# DS3_CONTROLLER_R.net
KiCad netlist of a schematic drawn in EasyEDA Pro
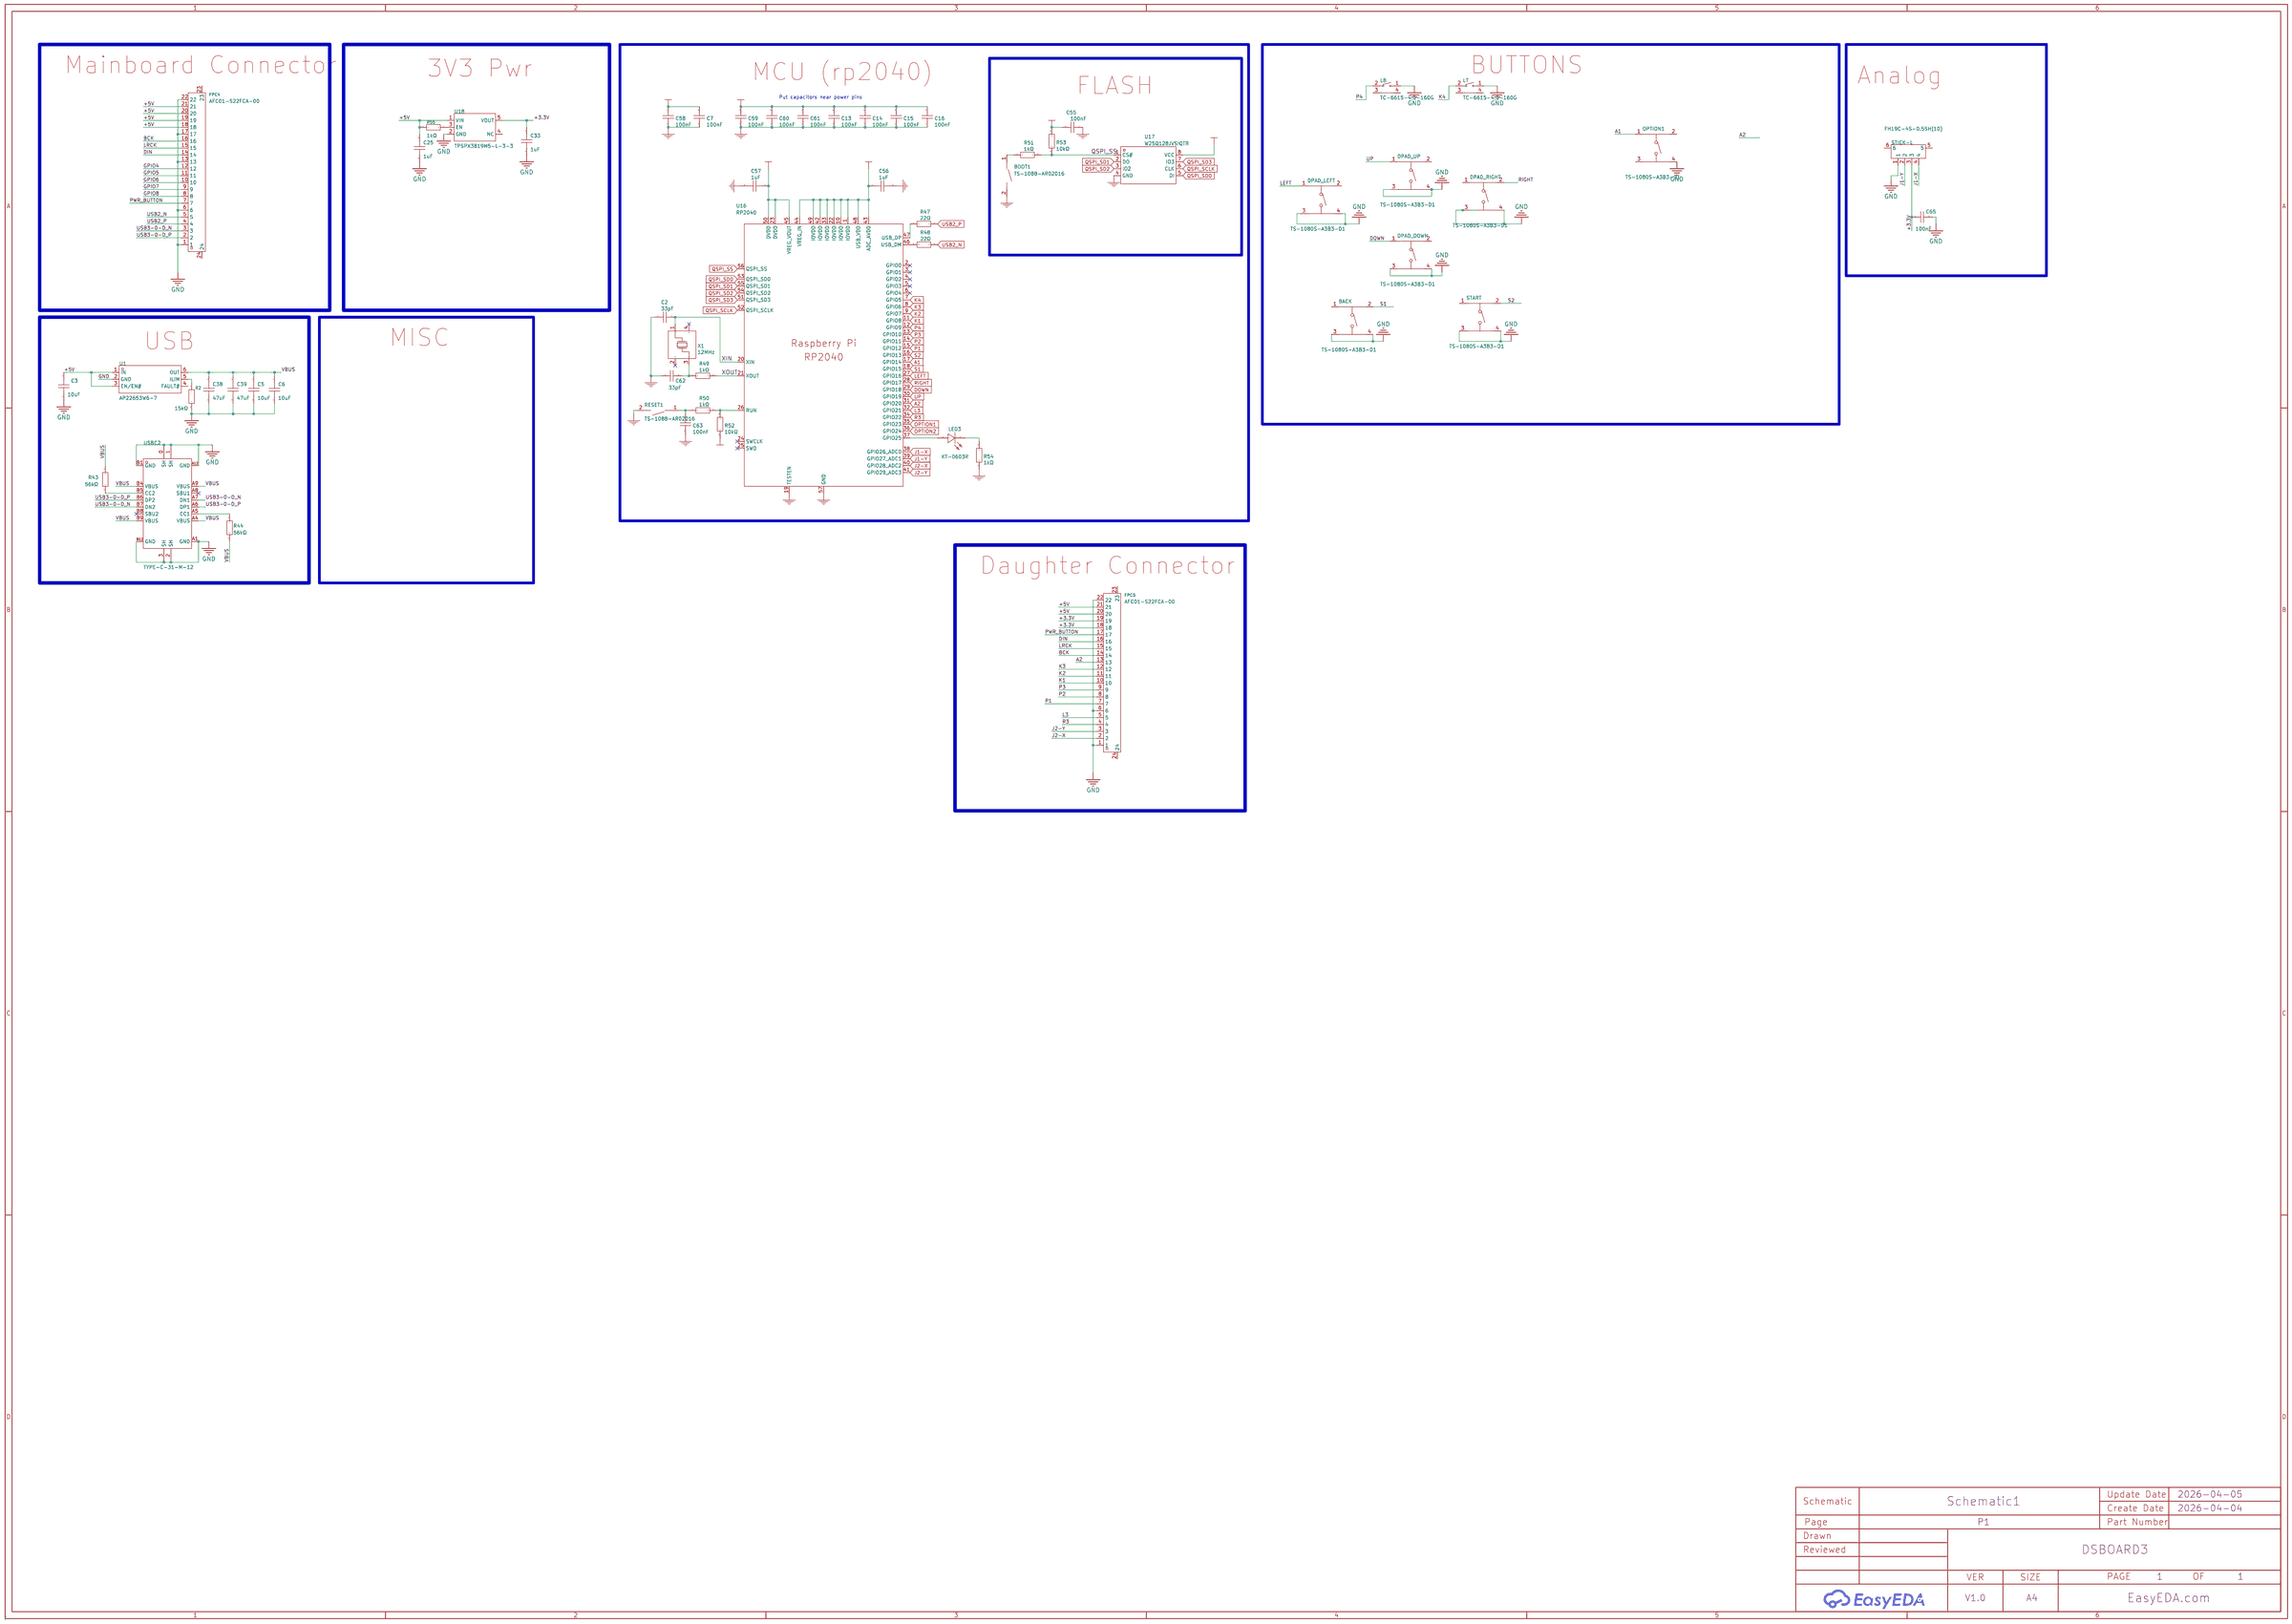
[diagram p0: schematic sheet]

(export (version "E")
  (design (tool "Eeschema 10.0.6"))
  (components
    (comp (ref "BACK")
      (value "TS-1080S-A3B3-D1")
      (footprint "easyedapro:KEY-SMD_4P-L6.0-W6.0-P4.50-LS9.5-BL")
      (fields (field (name "Manufacturer") "Yuandi(元迪)"))
      (libsource (lib "easyedapro") (part "K2-1102SP-C4SC-04"))
    )
    (comp (ref "BOOT1")
      (value "TS-1088-AR02016")
      (footprint "easyedapro:SW-SMD_L3.9-W3.0-P4.45")
      (fields (field (name "Manufacturer") "XUNPU(讯普)"))
      (libsource (lib "easyedapro") (part "TS-1088-AR02016"))
    )
    (comp (ref "C2")
      (value "33pF")
      (footprint "easyedapro:C0402")
      (fields (field (name "Manufacturer Part") "0402CG330J500NT") (field (name "Manufacturer") "FH(风华)"))
      (libsource (lib "easyedapro") (part "33pF"))
    )
    (comp (ref "C3")
      (value "10uF")
      (footprint "easyedapro:C0805")
      (fields
        (field (name "Manufacturer Part") "CL21A106KAYNNNE")
        (field (name "Manufacturer") "SAMSUNG(三星)")
      )
      (libsource (lib "easyedapro") (part "CL21A106KAYNNNE"))
    )
    (comp (ref "C5")
      (value "10uF")
      (footprint "easyedapro:C0805")
      (fields
        (field (name "Manufacturer Part") "CL21A106KAYNNNE")
        (field (name "Manufacturer") "SAMSUNG(三星)")
      )
      (libsource (lib "easyedapro") (part "CL21A106KAYNNNE"))
    )
    (comp (ref "C6")
      (value "10uF")
      (footprint "easyedapro:C0805")
      (fields
        (field (name "Manufacturer Part") "CL21A106KAYNNNE")
        (field (name "Manufacturer") "SAMSUNG(三星)")
      )
      (libsource (lib "easyedapro") (part "CL21A106KAYNNNE"))
    )
    (comp (ref "C7")
      (value "100nF")
      (footprint "easyedapro:C0402_NEW")
      (fields
        (field (name "Manufacturer Part") "CL05B104KO5NNNC")
        (field (name "Manufacturer") "SAMSUNG(三星)")
      )
      (libsource (lib "easyedapro") (part "100nF"))
    )
    (comp (ref "C13")
      (value "100nF")
      (footprint "easyedapro:C0402_NEW")
      (fields
        (field (name "Manufacturer Part") "CL05B104KO5NNNC")
        (field (name "Manufacturer") "SAMSUNG(三星)")
      )
      (libsource (lib "easyedapro") (part "100nF"))
    )
    (comp (ref "C14")
      (value "100nF")
      (footprint "easyedapro:C0402_NEW")
      (fields
        (field (name "Manufacturer Part") "CL05B104KO5NNNC")
        (field (name "Manufacturer") "SAMSUNG(三星)")
      )
      (libsource (lib "easyedapro") (part "100nF"))
    )
    (comp (ref "C15")
      (value "100nF")
      (footprint "easyedapro:C0402_NEW")
      (fields
        (field (name "Manufacturer Part") "CL05B104KO5NNNC")
        (field (name "Manufacturer") "SAMSUNG(三星)")
      )
      (libsource (lib "easyedapro") (part "100nF"))
    )
    (comp (ref "C16")
      (value "100nF")
      (footprint "easyedapro:C0402_NEW")
      (fields
        (field (name "Manufacturer Part") "CL05B104KO5NNNC")
        (field (name "Manufacturer") "SAMSUNG(三星)")
      )
      (libsource (lib "easyedapro") (part "100nF"))
    )
    (comp (ref "C25")
      (value "1uF")
      (footprint "easyedapro:C0603")
      (fields
        (field (name "Manufacturer Part") "CL10A105KB8NNNC")
        (field (name "Manufacturer") "SAMSUNG(三星)")
      )
      (libsource (lib "easyedapro") (part "CL10A105KB8NNNC"))
    )
    (comp (ref "C33")
      (value "1uF")
      (footprint "easyedapro:C0603")
      (fields
        (field (name "Manufacturer Part") "CL10A105KB8NNNC")
        (field (name "Manufacturer") "SAMSUNG(三星)")
      )
      (libsource (lib "easyedapro") (part "CL10A105KB8NNNC"))
    )
    (comp (ref "C38")
      (value "47uF")
      (footprint "easyedapro:C1206")
      (fields
        (field (name "Manufacturer Part") "CL31A476MPHNNNE")
        (field (name "Manufacturer") "SAMSUNG(三星)")
      )
      (libsource (lib "easyedapro") (part "CL31A476MPHNNNE"))
    )
    (comp (ref "C39")
      (value "47uF")
      (footprint "easyedapro:C1206")
      (fields
        (field (name "Manufacturer Part") "CL31A476MPHNNNE")
        (field (name "Manufacturer") "SAMSUNG(三星)")
      )
      (libsource (lib "easyedapro") (part "CL31A476MPHNNNE"))
    )
    (comp (ref "C55")
      (value "100nF")
      (footprint "easyedapro:C0402_NEW")
      (fields
        (field (name "Manufacturer Part") "CL05B104KO5NNNC")
        (field (name "Manufacturer") "SAMSUNG(三星)")
      )
      (libsource (lib "easyedapro") (part "100nF"))
    )
    (comp (ref "C56")
      (value "1uF")
      (footprint "easyedapro:C0402")
      (fields
        (field (name "Manufacturer Part") "CL05A105KA5NQNC")
        (field (name "Manufacturer") "SAMSUNG(三星)")
      )
      (libsource (lib "easyedapro") (part "1uF"))
    )
    (comp (ref "C57")
      (value "1uF")
      (footprint "easyedapro:C0402")
      (fields
        (field (name "Manufacturer Part") "CL05A105KA5NQNC")
        (field (name "Manufacturer") "SAMSUNG(三星)")
      )
      (libsource (lib "easyedapro") (part "1uF"))
    )
    (comp (ref "C58")
      (value "100nF")
      (footprint "easyedapro:C0402_NEW")
      (fields
        (field (name "Manufacturer Part") "CL05B104KO5NNNC")
        (field (name "Manufacturer") "SAMSUNG(三星)")
      )
      (libsource (lib "easyedapro") (part "100nF"))
    )
    (comp (ref "C59")
      (value "100nF")
      (footprint "easyedapro:C0402_NEW")
      (fields
        (field (name "Manufacturer Part") "CL05B104KO5NNNC")
        (field (name "Manufacturer") "SAMSUNG(三星)")
      )
      (libsource (lib "easyedapro") (part "100nF"))
    )
    (comp (ref "C60")
      (value "100nF")
      (footprint "easyedapro:C0402_NEW")
      (fields
        (field (name "Manufacturer Part") "CL05B104KO5NNNC")
        (field (name "Manufacturer") "SAMSUNG(三星)")
      )
      (libsource (lib "easyedapro") (part "100nF"))
    )
    (comp (ref "C61")
      (value "100nF")
      (footprint "easyedapro:C0402_NEW")
      (fields
        (field (name "Manufacturer Part") "CL05B104KO5NNNC")
        (field (name "Manufacturer") "SAMSUNG(三星)")
      )
      (libsource (lib "easyedapro") (part "100nF"))
    )
    (comp (ref "C62")
      (value "33pF")
      (footprint "easyedapro:C0402")
      (fields (field (name "Manufacturer Part") "0402CG330J500NT") (field (name "Manufacturer") "FH(风华)"))
      (libsource (lib "easyedapro") (part "33pF"))
    )
    (comp (ref "C63")
      (value "100nF")
      (footprint "easyedapro:C0402_NEW")
      (fields
        (field (name "Manufacturer Part") "CL05B104KO5NNNC")
        (field (name "Manufacturer") "SAMSUNG(三星)")
      )
      (libsource (lib "easyedapro") (part "100nF"))
    )
    (comp (ref "C65")
      (value "100nF")
      (footprint "easyedapro:C0402_NEW")
      (fields
        (field (name "Manufacturer Part") "CL05B104KO5NNNC")
        (field (name "Manufacturer") "SAMSUNG(三星)")
      )
      (libsource (lib "easyedapro") (part "100nF"))
    )
    (comp (ref "DPAD_DOWN")
      (value "TS-1080S-A3B3-D1")
      (footprint "easyedapro:KEY-SMD_4P-L6.0-W6.0-P4.50-LS9.5-BL")
      (fields (field (name "Manufacturer") "Yuandi(元迪)"))
      (libsource (lib "easyedapro") (part "K2-1102SP-C4SC-04"))
    )
    (comp (ref "DPAD_LEFT")
      (value "TS-1080S-A3B3-D1")
      (footprint "easyedapro:KEY-SMD_4P-L6.0-W6.0-P4.50-LS9.5-BL")
      (fields (field (name "Manufacturer") "Yuandi(元迪)"))
      (libsource (lib "easyedapro") (part "K2-1102SP-C4SC-04"))
    )
    (comp (ref "DPAD_RIGHT")
      (value "TS-1080S-A3B3-D1")
      (footprint "easyedapro:KEY-SMD_4P-L6.0-W6.0-P4.50-LS9.5-BL")
      (fields (field (name "Manufacturer") "Yuandi(元迪)"))
      (libsource (lib "easyedapro") (part "K2-1102SP-C4SC-04"))
    )
    (comp (ref "DPAD_UP")
      (value "TS-1080S-A3B3-D1")
      (footprint "easyedapro:KEY-SMD_4P-L6.0-W6.0-P4.50-LS9.5-BL")
      (fields (field (name "Manufacturer") "Yuandi(元迪)"))
      (libsource (lib "easyedapro") (part "K2-1102SP-C4SC-04"))
    )
    (comp (ref "FPC4")
      (value "AFC01-S22FCA-00")
      (fields (field (name "Manufacturer") "JS(钜硕电子)"))
      (libsource (lib "easyedapro") (part "fh12-22s-0.5sh(55)"))
    )
    (comp (ref "FPC5")
      (value "AFC01-S22FCA-00")
      (fields (field (name "Manufacturer") "JS(钜硕电子)"))
      (libsource (lib "easyedapro") (part "fh12-22s-0.5sh(55)"))
    )
    (comp (ref "LB")
      (value "TC-6615-4.5-160G")
      (footprint "easyedapro:KEY-TH_TC-6615-4.5-160G")
      (fields (field (name "Manufacturer") "HCTL(华灿天禄)"))
      (libsource (lib "easyedapro") (part "TC-6615-4.5-160G"))
    )
    (comp (ref "LED3")
      (value "KT-0603R")
      (footprint "easyedapro:LED0603-RD")
      (fields (field (name "Manufacturer") "KENTO"))
      (libsource (lib "easyedapro") (part "KT-0603R"))
    )
    (comp (ref "LT")
      (value "TC-6615-4.5-160G")
      (footprint "easyedapro:KEY-TH_TC-6615-4.5-160G")
      (fields (field (name "Manufacturer") "HCTL(华灿天禄)"))
      (libsource (lib "easyedapro") (part "TC-6615-4.5-160G"))
    )
    (comp (ref "OPTION1")
      (value "TS-1080S-A3B3-D1")
      (footprint "easyedapro:KEY-SMD_4P-L6.0-W6.0-P4.50-LS9.5-BL")
      (fields (field (name "Manufacturer") "Yuandi(元迪)"))
      (libsource (lib "easyedapro") (part "K2-1102SP-C4SC-04"))
    )
    (comp (ref "R2")
      (value "15kΩ")
      (footprint "easyedapro:R0402")
      (fields
        (field (name "Manufacturer Part") "0402WGF1502TCE")
        (field (name "Manufacturer") "UNI-ROYAL(厚声)")
      )
      (libsource (lib "easyedapro") (part "0402WGF1502TCE"))
    )
    (comp (ref "R43")
      (value "56kΩ")
      (footprint "easyedapro:R0402")
      (fields
        (field (name "Manufacturer Part") "0402WGF5602TCE")
        (field (name "Manufacturer") "UNI-ROYAL(厚声)")
      )
      (libsource (lib "easyedapro") (part "0402WGF5602TCE"))
    )
    (comp (ref "R44")
      (value "56kΩ")
      (footprint "easyedapro:R0402")
      (fields
        (field (name "Manufacturer Part") "0402WGF5602TCE")
        (field (name "Manufacturer") "UNI-ROYAL(厚声)")
      )
      (libsource (lib "easyedapro") (part "0402WGF5602TCE"))
    )
    (comp (ref "R47")
      (value "22Ω")
      (footprint "easyedapro:R0402")
      (fields
        (field (name "Manufacturer Part") "0402WGF220JTCE")
        (field (name "Manufacturer") "UNI-ROYAL(厚声)")
      )
      (libsource (lib "easyedapro") (part "22Ω"))
    )
    (comp (ref "R48")
      (value "22Ω")
      (footprint "easyedapro:R0402")
      (fields
        (field (name "Manufacturer Part") "0402WGF220JTCE")
        (field (name "Manufacturer") "UNI-ROYAL(厚声)")
      )
      (libsource (lib "easyedapro") (part "22Ω"))
    )
    (comp (ref "R49")
      (value "1kΩ")
      (footprint "easyedapro:R0402")
      (fields
        (field (name "Manufacturer Part") "0402WGF1001TCE")
        (field (name "Manufacturer") "UNI-ROYAL(厚声)")
      )
      (libsource (lib "easyedapro") (part "1kΩ"))
    )
    (comp (ref "R50")
      (value "1kΩ")
      (footprint "easyedapro:R0402")
      (fields
        (field (name "Manufacturer Part") "0402WGF1001TCE")
        (field (name "Manufacturer") "UNI-ROYAL(厚声)")
      )
      (libsource (lib "easyedapro") (part "1kΩ"))
    )
    (comp (ref "R51")
      (value "1kΩ")
      (footprint "easyedapro:R0402")
      (fields
        (field (name "Manufacturer Part") "0402WGF1001TCE")
        (field (name "Manufacturer") "UNI-ROYAL(厚声)")
      )
      (libsource (lib "easyedapro") (part "1kΩ"))
    )
    (comp (ref "R52")
      (value "10kΩ")
      (footprint "easyedapro:R0402")
      (fields
        (field (name "Manufacturer Part") "0402WGF1002TCE")
        (field (name "Manufacturer") "UNI-ROYAL(厚声)")
      )
      (libsource (lib "easyedapro") (part "10kΩ"))
    )
    (comp (ref "R53")
      (value "10kΩ")
      (footprint "easyedapro:R0402")
      (fields
        (field (name "Manufacturer Part") "0402WGF1002TCE")
        (field (name "Manufacturer") "UNI-ROYAL(厚声)")
      )
      (libsource (lib "easyedapro") (part "10kΩ"))
    )
    (comp (ref "R54")
      (value "1kΩ")
      (footprint "easyedapro:R0402")
      (fields
        (field (name "Manufacturer Part") "0402WGF1001TCE")
        (field (name "Manufacturer") "UNI-ROYAL(厚声)")
      )
      (libsource (lib "easyedapro") (part "1kΩ"))
    )
    (comp (ref "R55")
      (value "1kΩ")
      (footprint "easyedapro:R0402")
      (fields
        (field (name "Manufacturer Part") "0402WGF1001TCE")
        (field (name "Manufacturer") "UNI-ROYAL(厚声)")
      )
      (libsource (lib "easyedapro") (part "0402WGF1001TCE"))
    )
    (comp (ref "RESET1")
      (value "TS-1088-AR02016")
      (footprint "easyedapro:SW-SMD_L3.9-W3.0-P4.45")
      (fields (field (name "Manufacturer") "XUNPU(讯普)"))
      (libsource (lib "easyedapro") (part "TS-1088-AR02016"))
    )
    (comp (ref "START")
      (value "TS-1080S-A3B3-D1")
      (footprint "easyedapro:KEY-SMD_4P-L6.0-W6.0-P4.50-LS9.5-BL")
      (fields (field (name "Manufacturer") "Yuandi(元迪)"))
      (libsource (lib "easyedapro") (part "K2-1102SP-C4SC-04"))
    )
    (comp (ref "STICK-L")
      (value "FH19C-4S-0.5SH(10)")
      (fields (field (name "Manufacturer") "HRS(广濑)"))
      (libsource (lib "easyedapro") (part "fh34srj-4s-0.5sh(50)"))
    )
    (comp (ref "U1")
      (value "AP22653W6-7")
      (footprint "easyedapro:SOT-23-6_L2.9-W1.6-P0.95-LS2.8-BR")
      (fields (field (name "Manufacturer") "DIODES(美台)"))
      (libsource (lib "easyedapro") (part "AP22653W6-7"))
    )
    (comp (ref "U16")
      (value "RP2040")
      (footprint "easyedapro:LQFN-56_L7.0-W7.0-P0.4-EP")
      (fields (field (name "Manufacturer") "Raspberry Pi(树莓派)"))
      (libsource (lib "easyedapro") (part "RP2040"))
    )
    (comp (ref "U17")
      (value "W25Q128JVSIQTR")
      (footprint "easyedapro:SOIC-8_L5.3-W5.3-P1.27-LS8.0-BL")
      (fields (field (name "Manufacturer Part") "W25Q128JVSIQ") (field (name "Manufacturer") "WINBOND(华邦)"))
      (libsource (lib "easyedapro") (part "W25Q128JVSIQTR"))
    )
    (comp (ref "U18")
      (value "TPSPX3819M5-L-3-3")
      (footprint "easyedapro:SOT-23-5_L3.0-W1.6-P0.95-LS2.8-BR")
      (fields (field (name "Manufacturer") "TECH PUBLIC(台舟)"))
      (libsource (lib "easyedapro") (part "TPSPX3819M5-L-3-3"))
    )
    (comp (ref "USBC2")
      (value "TYPE-C-31-M-12")
      (footprint "easyedapro:USB-C_SMD-TYPE-C-31-M-12")
      (fields (field (name "Manufacturer") "韩国韩荣"))
      (libsource (lib "easyedapro") (part "TYPE-C-31-M-12"))
    )
    (comp (ref "X1")
      (value "12MHz")
      (footprint "easyedapro:OSC-SMD_4P-L3.2-W2.5-BL")
      (fields (field (name "Manufacturer Part") "X322512MSB4SI") (field (name "Manufacturer") "YXC"))
      (libsource (lib "easyedapro") (part "12MHz"))
    )
  )
  (nets
    (net (code "1") (name "+1V1") (class "Default")
      (node (ref "C57") (pin "1") (pinfunction "1_1") (pintype "unspecified"))
      (node (ref "C58") (pin "2") (pinfunction "2_2") (pintype "input"))
      (node (ref "C7") (pin "2") (pinfunction "2_2") (pintype "input"))
      (node (ref "U16") (pin "23") (pinfunction "DVDD_23") (pintype "bidirectional"))
      (node (ref "U16") (pin "45") (pinfunction "VREG_VOUT_45") (pintype "bidirectional"))
      (node (ref "U16") (pin "50") (pinfunction "DVDD_50") (pintype "bidirectional"))
    )
    (net (code "2") (name "+3.3V") (class "Default")
      (node (ref "C13") (pin "2") (pinfunction "2_2") (pintype "input"))
      (node (ref "C14") (pin "2") (pinfunction "2_2") (pintype "input"))
      (node (ref "C15") (pin "2") (pinfunction "2_2") (pintype "input"))
      (node (ref "C16") (pin "2") (pinfunction "2_2") (pintype "input"))
      (node (ref "C33") (pin "1") (pinfunction "1_1") (pintype "unspecified"))
      (node (ref "C55") (pin "2") (pinfunction "2_2") (pintype "input"))
      (node (ref "C56") (pin "1") (pinfunction "1_1") (pintype "unspecified"))
      (node (ref "C59") (pin "2") (pinfunction "2_2") (pintype "input"))
      (node (ref "C60") (pin "2") (pinfunction "2_2") (pintype "input"))
      (node (ref "C61") (pin "2") (pinfunction "2_2") (pintype "input"))
      (node (ref "C65") (pin "1") (pinfunction "1_1") (pintype "input"))
      (node (ref "FPC5") (pin "18") (pinfunction "18_18") (pintype "input"))
      (node (ref "FPC5") (pin "19") (pinfunction "19_19") (pintype "input"))
      (node (ref "R52") (pin "1") (pinfunction "1_1") (pintype "input"))
      (node (ref "R53") (pin "2") (pinfunction "2_2") (pintype "input"))
      (node (ref "STICK-L") (pin "3") (pinfunction "3_3") (pintype "unspecified"))
      (node (ref "U16") (pin "1") (pinfunction "IOVDD_1") (pintype "bidirectional"))
      (node (ref "U16") (pin "10") (pinfunction "IOVDD_10") (pintype "bidirectional"))
      (node (ref "U16") (pin "22") (pinfunction "IOVDD_22") (pintype "bidirectional"))
      (node (ref "U16") (pin "33") (pinfunction "IOVDD_33") (pintype "bidirectional"))
      (node (ref "U16") (pin "42") (pinfunction "IOVDD_42") (pintype "bidirectional"))
      (node (ref "U16") (pin "43") (pinfunction "ADC_AVDD_43") (pintype "bidirectional"))
      (node (ref "U16") (pin "44") (pinfunction "VREG_IN_44") (pintype "bidirectional"))
      (node (ref "U16") (pin "48") (pinfunction "USB_VDD_48") (pintype "bidirectional"))
      (node (ref "U16") (pin "49") (pinfunction "IOVDD_49") (pintype "bidirectional"))
      (node (ref "U17") (pin "8") (pinfunction "VCC_8") (pintype "unspecified"))
      (node (ref "U18") (pin "5") (pinfunction "VOUT_5") (pintype "unspecified"))
    )
    (net (code "3") (name "/+5V") (class "Default")
      (node (ref "C25") (pin "1") (pinfunction "1_1") (pintype "unspecified"))
      (node (ref "C3") (pin "1") (pinfunction "1_1") (pintype "unspecified"))
      (node (ref "FPC4") (pin "18") (pinfunction "18_18") (pintype "input"))
      (node (ref "FPC4") (pin "19") (pinfunction "19_19") (pintype "input"))
      (node (ref "FPC4") (pin "20") (pinfunction "20_20") (pintype "input"))
      (node (ref "FPC4") (pin "21") (pinfunction "21_21") (pintype "input"))
      (node (ref "FPC5") (pin "20") (pinfunction "20_20") (pintype "input"))
      (node (ref "FPC5") (pin "21") (pinfunction "21_21") (pintype "input"))
      (node (ref "R55") (pin "1") (pinfunction "1_1") (pintype "input"))
      (node (ref "U1") (pin "1") (pinfunction "IN_1") (pintype "unspecified"))
      (node (ref "U1") (pin "3") (pinfunction "EN/EN#_3") (pintype "unspecified"))
      (node (ref "U18") (pin "1") (pinfunction "VIN_1") (pintype "unspecified"))
    )
    (net (code "4") (name "/BCK") (class "Default")
      (node (ref "FPC4") (pin "16") (pinfunction "16_16") (pintype "input"))
      (node (ref "FPC5") (pin "14") (pinfunction "14_14") (pintype "input"))
    )
    (net (code "5") (name "/DIN") (class "Default")
      (node (ref "FPC4") (pin "14") (pinfunction "14_14") (pintype "input"))
      (node (ref "FPC5") (pin "16") (pinfunction "16_16") (pintype "input"))
    )
    (net (code "6") (name "/GPIO4") (class "Default")
      (node (ref "FPC4") (pin "12") (pinfunction "12_12") (pintype "input"))
    )
    (net (code "7") (name "/GPIO5") (class "Default")
      (node (ref "FPC4") (pin "11") (pinfunction "11_11") (pintype "input"))
    )
    (net (code "8") (name "/GPIO6") (class "Default")
      (node (ref "FPC4") (pin "10") (pinfunction "10_10") (pintype "input"))
    )
    (net (code "9") (name "/GPIO7") (class "Default")
      (node (ref "FPC4") (pin "9") (pinfunction "9_9") (pintype "input"))
    )
    (net (code "10") (name "/GPIO8") (class "Default")
      (node (ref "FPC4") (pin "8") (pinfunction "8_8") (pintype "input"))
    )
    (net (code "11") (name "/LRCK") (class "Default")
      (node (ref "FPC4") (pin "15") (pinfunction "15_15") (pintype "input"))
      (node (ref "FPC5") (pin "15") (pinfunction "15_15") (pintype "input"))
    )
    (net (code "12") (name "/PWR_BUTTON") (class "Default")
      (node (ref "FPC4") (pin "7") (pinfunction "7_7") (pintype "input"))
      (node (ref "FPC5") (pin "17") (pinfunction "17_17") (pintype "input"))
    )
    (net (code "13") (name "/USB3-0-D_N") (class "Default")
      (node (ref "FPC4") (pin "3") (pinfunction "3_3") (pintype "input"))
      (node (ref "USBC2") (pin "A7") (pinfunction "DN1_A7") (pintype "unspecified"))
      (node (ref "USBC2") (pin "B7") (pinfunction "DN2_B7") (pintype "unspecified"))
    )
    (net (code "14") (name "/USB3-0-D_P") (class "Default")
      (node (ref "FPC4") (pin "2") (pinfunction "2_2") (pintype "input"))
      (node (ref "USBC2") (pin "A6") (pinfunction "DP1_A6") (pintype "unspecified"))
      (node (ref "USBC2") (pin "B6") (pinfunction "DP2_B6") (pintype "unspecified"))
    )
    (net (code "15") (name "/VBUS") (class "Default")
      (node (ref "C38") (pin "1") (pinfunction "1_1") (pintype "unspecified"))
      (node (ref "C39") (pin "1") (pinfunction "1_1") (pintype "unspecified"))
      (node (ref "C5") (pin "1") (pinfunction "1_1") (pintype "unspecified"))
      (node (ref "C6") (pin "1") (pinfunction "1_1") (pintype "unspecified"))
      (node (ref "R43") (pin "2") (pinfunction "2_2") (pintype "input"))
      (node (ref "R44") (pin "2") (pinfunction "2_2") (pintype "input"))
      (node (ref "U1") (pin "6") (pinfunction "OUT_6") (pintype "unspecified"))
      (node (ref "USBC2") (pin "A4") (pinfunction "VBUS_A4") (pintype "unspecified"))
      (node (ref "USBC2") (pin "A9") (pinfunction "VBUS_A9") (pintype "unspecified"))
      (node (ref "USBC2") (pin "B4") (pinfunction "VBUS_B4") (pintype "unspecified"))
      (node (ref "USBC2") (pin "B9") (pinfunction "VBUS_B9") (pintype "unspecified"))
    )
    (net (code "16") (name "/XIN") (class "Default")
      (node (ref "C2") (pin "2") (pinfunction "2_2") (pintype "input"))
      (node (ref "U16") (pin "20") (pinfunction "XIN_20") (pintype "input"))
      (node (ref "X1") (pin "1") (pinfunction "OSC1_1") (pintype "unspecified"))
    )
    (net (code "17") (name "/XOUT") (class "Default")
      (node (ref "R49") (pin "2") (pinfunction "2_2") (pintype "input"))
      (node (ref "U16") (pin "21") (pinfunction "XOUT_21") (pintype "unspecified"))
    )
    (net (code "18") (name "A1") (class "Default")
      (node (ref "OPTION1") (pin "1") (pinfunction "1_1") (pintype "unspecified"))
      (node (ref "U16") (pin "17") (pinfunction "GPIO14_17") (pintype "bidirectional"))
    )
    (net (code "19") (name "A2") (class "Default")
      (node (ref "FPC5") (pin "13") (pinfunction "13_13") (pintype "input"))
      (node (ref "U16") (pin "31") (pinfunction "GPIO20_31") (pintype "bidirectional"))
    )
    (net (code "20") (name "DOWN") (class "Default")
      (node (ref "DPAD_DOWN") (pin "1") (pinfunction "1_1") (pintype "unspecified"))
      (node (ref "U16") (pin "29") (pinfunction "GPIO18_29") (pintype "bidirectional"))
    )
    (net (code "21") (name "GND") (class "Default")
      (node (ref "BACK") (pin "3") (pinfunction "3_3") (pintype "unspecified"))
      (node (ref "BACK") (pin "4") (pinfunction "4_4") (pintype "unspecified"))
      (node (ref "BOOT1") (pin "2") (pinfunction "2_2") (pintype "unspecified"))
      (node (ref "C13") (pin "1") (pinfunction "1_1") (pintype "input"))
      (node (ref "C14") (pin "1") (pinfunction "1_1") (pintype "input"))
      (node (ref "C15") (pin "1") (pinfunction "1_1") (pintype "input"))
      (node (ref "C16") (pin "1") (pinfunction "1_1") (pintype "input"))
      (node (ref "C2") (pin "1") (pinfunction "1_1") (pintype "input"))
      (node (ref "C25") (pin "2") (pinfunction "2_2") (pintype "unspecified"))
      (node (ref "C3") (pin "2") (pinfunction "2_2") (pintype "unspecified"))
      (node (ref "C33") (pin "2") (pinfunction "2_2") (pintype "unspecified"))
      (node (ref "C38") (pin "2") (pinfunction "2_2") (pintype "unspecified"))
      (node (ref "C39") (pin "2") (pinfunction "2_2") (pintype "unspecified"))
      (node (ref "C5") (pin "2") (pinfunction "2_2") (pintype "unspecified"))
      (node (ref "C55") (pin "1") (pinfunction "1_1") (pintype "input"))
      (node (ref "C56") (pin "2") (pinfunction "2_2") (pintype "unspecified"))
      (node (ref "C57") (pin "2") (pinfunction "2_2") (pintype "unspecified"))
      (node (ref "C58") (pin "1") (pinfunction "1_1") (pintype "input"))
      (node (ref "C59") (pin "1") (pinfunction "1_1") (pintype "input"))
      (node (ref "C6") (pin "2") (pinfunction "2_2") (pintype "unspecified"))
      (node (ref "C60") (pin "1") (pinfunction "1_1") (pintype "input"))
      (node (ref "C61") (pin "1") (pinfunction "1_1") (pintype "input"))
      (node (ref "C62") (pin "1") (pinfunction "1_1") (pintype "input"))
      (node (ref "C63") (pin "1") (pinfunction "1_1") (pintype "input"))
      (node (ref "C65") (pin "2") (pinfunction "2_2") (pintype "input"))
      (node (ref "C7") (pin "1") (pinfunction "1_1") (pintype "input"))
      (node (ref "DPAD_DOWN") (pin "3") (pinfunction "3_3") (pintype "unspecified"))
      (node (ref "DPAD_DOWN") (pin "4") (pinfunction "4_4") (pintype "unspecified"))
      (node (ref "DPAD_LEFT") (pin "3") (pinfunction "3_3") (pintype "unspecified"))
      (node (ref "DPAD_LEFT") (pin "4") (pinfunction "4_4") (pintype "unspecified"))
      (node (ref "DPAD_RIGHT") (pin "3") (pinfunction "3_3") (pintype "unspecified"))
      (node (ref "DPAD_RIGHT") (pin "4") (pinfunction "4_4") (pintype "unspecified"))
      (node (ref "DPAD_UP") (pin "3") (pinfunction "3_3") (pintype "unspecified"))
      (node (ref "DPAD_UP") (pin "4") (pinfunction "4_4") (pintype "unspecified"))
      (node (ref "FPC4") (pin "1") (pinfunction "1_1") (pintype "input"))
      (node (ref "FPC4") (pin "13") (pinfunction "13_13") (pintype "input"))
      (node (ref "FPC4") (pin "17") (pinfunction "17_17") (pintype "input"))
      (node (ref "FPC4") (pin "22") (pinfunction "22_22") (pintype "input"))
      (node (ref "FPC4") (pin "6") (pinfunction "6_6") (pintype "input"))
      (node (ref "FPC5") (pin "1") (pinfunction "1_1") (pintype "input"))
      (node (ref "FPC5") (pin "22") (pinfunction "22_22") (pintype "input"))
      (node (ref "FPC5") (pin "6") (pinfunction "6_6") (pintype "input"))
      (node (ref "LB") (pin "1") (pinfunction "1_1") (pintype "unspecified"))
      (node (ref "LT") (pin "1") (pinfunction "1_1") (pintype "unspecified"))
      (node (ref "OPTION1") (pin "4") (pinfunction "4_4") (pintype "unspecified"))
      (node (ref "R2") (pin "2") (pinfunction "2_2") (pintype "input"))
      (node (ref "R54") (pin "1") (pinfunction "1_1") (pintype "input"))
      (node (ref "RESET1") (pin "2") (pinfunction "2_2") (pintype "unspecified"))
      (node (ref "START") (pin "3") (pinfunction "3_3") (pintype "unspecified"))
      (node (ref "START") (pin "4") (pinfunction "4_4") (pintype "unspecified"))
      (node (ref "STICK-L") (pin "1") (pinfunction "1_1") (pintype "unspecified"))
      (node (ref "U1") (pin "2") (pinfunction "GND_2") (pintype "unspecified"))
      (node (ref "U16") (pin "19") (pinfunction "TESTEN_19") (pintype "unspecified"))
      (node (ref "U16") (pin "57") (pinfunction "GND_57") (pintype "bidirectional"))
      (node (ref "U17") (pin "4") (pinfunction "GND_4") (pintype "unspecified"))
      (node (ref "U18") (pin "2") (pinfunction "GND_2") (pintype "unspecified"))
      (node (ref "USBC2") (pin "0") (pinfunction "SH_0") (pintype "unspecified"))
      (node (ref "USBC2") (pin "1") (pinfunction "SH_1") (pintype "unspecified"))
      (node (ref "USBC2") (pin "2") (pinfunction "SH_2") (pintype "unspecified"))
      (node (ref "USBC2") (pin "3") (pinfunction "SH_3") (pintype "unspecified"))
      (node (ref "USBC2") (pin "A1") (pinfunction "GND_A1") (pintype "unspecified"))
      (node (ref "USBC2") (pin "A12") (pinfunction "GND_A12") (pintype "unspecified"))
      (node (ref "USBC2") (pin "B1") (pinfunction "GND_B1") (pintype "unspecified"))
      (node (ref "USBC2") (pin "B12") (pinfunction "GND_B12") (pintype "unspecified"))
    )
    (net (code "22") (name "J1-X") (class "Default")
      (node (ref "STICK-L") (pin "4") (pinfunction "4_4") (pintype "unspecified"))
      (node (ref "U16") (pin "38") (pinfunction "GPIO26_ADC0_38") (pintype "bidirectional"))
    )
    (net (code "23") (name "J1-Y") (class "Default")
      (node (ref "STICK-L") (pin "2") (pinfunction "2_2") (pintype "unspecified"))
      (node (ref "U16") (pin "39") (pinfunction "GPIO27_ADC1_39") (pintype "bidirectional"))
    )
    (net (code "24") (name "J2-X") (class "Default")
      (node (ref "FPC5") (pin "2") (pinfunction "2_2") (pintype "input"))
      (node (ref "U16") (pin "40") (pinfunction "GPIO28_ADC2_40") (pintype "bidirectional"))
    )
    (net (code "25") (name "J2-Y") (class "Default")
      (node (ref "FPC5") (pin "3") (pinfunction "3_3") (pintype "input"))
      (node (ref "U16") (pin "41") (pinfunction "GPIO29_ADC3_41") (pintype "bidirectional"))
    )
    (net (code "26") (name "K1") (class "Default")
      (node (ref "FPC5") (pin "10") (pinfunction "10_10") (pintype "input"))
      (node (ref "U16") (pin "11") (pinfunction "GPIO8_11") (pintype "bidirectional"))
    )
    (net (code "27") (name "K2") (class "Default")
      (node (ref "FPC5") (pin "11") (pinfunction "11_11") (pintype "input"))
      (node (ref "U16") (pin "9") (pinfunction "GPIO7_9") (pintype "bidirectional"))
    )
    (net (code "28") (name "K3") (class "Default")
      (node (ref "FPC5") (pin "12") (pinfunction "12_12") (pintype "input"))
      (node (ref "U16") (pin "8") (pinfunction "GPIO6_8") (pintype "bidirectional"))
    )
    (net (code "29") (name "K4") (class "Default")
      (node (ref "LT") (pin "2") (pinfunction "2_2") (pintype "unspecified"))
      (node (ref "U16") (pin "7") (pinfunction "GPIO5_7") (pintype "bidirectional"))
    )
    (net (code "30") (name "L3") (class "Default")
      (node (ref "FPC5") (pin "5") (pinfunction "5_5") (pintype "input"))
      (node (ref "U16") (pin "32") (pinfunction "GPIO21_32") (pintype "bidirectional"))
    )
    (net (code "31") (name "LEFT") (class "Default")
      (node (ref "DPAD_LEFT") (pin "1") (pinfunction "1_1") (pintype "unspecified"))
      (node (ref "U16") (pin "27") (pinfunction "GPIO16_27") (pintype "bidirectional"))
    )
    (net (code "32") (name "Net-(BOOT1-Pad1)") (class "Default")
      (node (ref "BOOT1") (pin "1") (pinfunction "1_1") (pintype "unspecified"))
      (node (ref "R51") (pin "1") (pinfunction "1_1") (pintype "input"))
    )
    (net (code "33") (name "Net-(C63-Pad2)") (class "Default")
      (node (ref "C63") (pin "2") (pinfunction "2_2") (pintype "input"))
      (node (ref "R50") (pin "1") (pinfunction "1_1") (pintype "input"))
      (node (ref "RESET1") (pin "1") (pinfunction "1_1") (pintype "unspecified"))
    )
    (net (code "34") (name "Net-(LED3-A)") (class "Default")
      (node (ref "LED3") (pin "2") (pinfunction "A_2") (pintype "unspecified"))
      (node (ref "U16") (pin "37") (pinfunction "GPIO25_37") (pintype "bidirectional"))
    )
    (net (code "35") (name "Net-(LED3-K)") (class "Default")
      (node (ref "LED3") (pin "1") (pinfunction "K_1") (pintype "unspecified"))
      (node (ref "R54") (pin "2") (pinfunction "2_2") (pintype "input"))
    )
    (net (code "36") (name "Net-(U1-ILIM)") (class "Default")
      (node (ref "R2") (pin "1") (pinfunction "1_1") (pintype "input"))
      (node (ref "U1") (pin "5") (pinfunction "ILIM_5") (pintype "unspecified"))
    )
    (net (code "37") (name "Net-(U16-RUN)") (class "Default")
      (node (ref "R50") (pin "2") (pinfunction "2_2") (pintype "input"))
      (node (ref "R52") (pin "2") (pinfunction "2_2") (pintype "input"))
      (node (ref "U16") (pin "26") (pinfunction "RUN_26") (pintype "input"))
    )
    (net (code "38") (name "Net-(U16-USB_DM)") (class "Default")
      (node (ref "R48") (pin "1") (pinfunction "1_1") (pintype "input"))
      (node (ref "U16") (pin "46") (pinfunction "USB_DM_46") (pintype "bidirectional"))
    )
    (net (code "39") (name "Net-(U16-USB_DP)") (class "Default")
      (node (ref "R47") (pin "2") (pinfunction "2_2") (pintype "input"))
      (node (ref "U16") (pin "47") (pinfunction "USB_DP_47") (pintype "bidirectional"))
    )
    (net (code "40") (name "Net-(U18-EN)") (class "Default")
      (node (ref "R55") (pin "2") (pinfunction "2_2") (pintype "input"))
      (node (ref "U18") (pin "3") (pinfunction "EN_3") (pintype "unspecified"))
    )
    (net (code "41") (name "Net-(USBC2-CC1)") (class "Default")
      (node (ref "R44") (pin "1") (pinfunction "1_1") (pintype "input"))
      (node (ref "USBC2") (pin "A5") (pinfunction "CC1_A5") (pintype "unspecified"))
    )
    (net (code "42") (name "Net-(USBC2-CC2)") (class "Default")
      (node (ref "R43") (pin "1") (pinfunction "1_1") (pintype "input"))
      (node (ref "USBC2") (pin "B5") (pinfunction "CC2_B5") (pintype "unspecified"))
    )
    (net (code "43") (name "Net-(X1-OSC2)") (class "Default")
      (node (ref "C62") (pin "2") (pinfunction "2_2") (pintype "input"))
      (node (ref "R49") (pin "1") (pinfunction "1_1") (pintype "input"))
      (node (ref "X1") (pin "3") (pinfunction "OSC2_3") (pintype "unspecified"))
    )
    (net (code "44") (name "OPTION1") (class "Default")
      (node (ref "U16") (pin "35") (pinfunction "GPIO23_35") (pintype "bidirectional"))
    )
    (net (code "45") (name "OPTION2") (class "Default")
      (node (ref "U16") (pin "36") (pinfunction "GPIO24_36") (pintype "bidirectional"))
    )
    (net (code "46") (name "P1") (class "Default")
      (node (ref "FPC5") (pin "7") (pinfunction "7_7") (pintype "input"))
      (node (ref "U16") (pin "15") (pinfunction "GPIO12_15") (pintype "bidirectional"))
    )
    (net (code "47") (name "P2") (class "Default")
      (node (ref "FPC5") (pin "8") (pinfunction "8_8") (pintype "input"))
      (node (ref "U16") (pin "14") (pinfunction "GPIO11_14") (pintype "bidirectional"))
    )
    (net (code "48") (name "P3") (class "Default")
      (node (ref "FPC5") (pin "9") (pinfunction "9_9") (pintype "input"))
      (node (ref "U16") (pin "13") (pinfunction "GPIO10_13") (pintype "bidirectional"))
    )
    (net (code "49") (name "P4") (class "Default")
      (node (ref "LB") (pin "2") (pinfunction "2_2") (pintype "unspecified"))
      (node (ref "U16") (pin "12") (pinfunction "GPIO9_12") (pintype "bidirectional"))
    )
    (net (code "50") (name "QSPI_SCLK") (class "Default")
      (node (ref "U16") (pin "52") (pinfunction "QSPI_SCLK_52") (pintype "output"))
      (node (ref "U17") (pin "6") (pinfunction "CLK_6") (pintype "unspecified"))
    )
    (net (code "51") (name "QSPI_SD0") (class "Default")
      (node (ref "U16") (pin "53") (pinfunction "QSPI_SD0_53") (pintype "bidirectional"))
      (node (ref "U17") (pin "5") (pinfunction "DI_5") (pintype "unspecified"))
    )
    (net (code "52") (name "QSPI_SD1") (class "Default")
      (node (ref "U16") (pin "55") (pinfunction "QSPI_SD1_55") (pintype "bidirectional"))
      (node (ref "U17") (pin "2") (pinfunction "DO_2") (pintype "unspecified"))
    )
    (net (code "53") (name "QSPI_SD2") (class "Default")
      (node (ref "U16") (pin "54") (pinfunction "QSPI_SD2_54") (pintype "bidirectional"))
      (node (ref "U17") (pin "3") (pinfunction "IO2_3") (pintype "unspecified"))
    )
    (net (code "54") (name "QSPI_SD3") (class "Default")
      (node (ref "U16") (pin "51") (pinfunction "QSPI_SD3_51") (pintype "bidirectional"))
      (node (ref "U17") (pin "7") (pinfunction "IO3_7") (pintype "unspecified"))
    )
    (net (code "55") (name "QSPI_SS") (class "Default")
      (node (ref "R51") (pin "2") (pinfunction "2_2") (pintype "input"))
      (node (ref "R53") (pin "1") (pinfunction "1_1") (pintype "input"))
      (node (ref "U16") (pin "56") (pinfunction "QSPI_SS_56") (pintype "bidirectional"))
      (node (ref "U17") (pin "1") (pinfunction "CS#_1") (pintype "unspecified"))
    )
    (net (code "56") (name "R3") (class "Default")
      (node (ref "FPC5") (pin "4") (pinfunction "4_4") (pintype "input"))
      (node (ref "U16") (pin "34") (pinfunction "GPIO22_34") (pintype "bidirectional"))
    )
    (net (code "57") (name "RIGHT") (class "Default")
      (node (ref "DPAD_RIGHT") (pin "2") (pinfunction "2_2") (pintype "unspecified"))
      (node (ref "U16") (pin "28") (pinfunction "GPIO17_28") (pintype "bidirectional"))
    )
    (net (code "58") (name "S1") (class "Default")
      (node (ref "BACK") (pin "2") (pinfunction "2_2") (pintype "unspecified"))
      (node (ref "U16") (pin "18") (pinfunction "GPIO15_18") (pintype "bidirectional"))
    )
    (net (code "59") (name "S2") (class "Default")
      (node (ref "START") (pin "2") (pinfunction "2_2") (pintype "unspecified"))
      (node (ref "U16") (pin "16") (pinfunction "GPIO13_16") (pintype "bidirectional"))
    )
    (net (code "60") (name "UP") (class "Default")
      (node (ref "DPAD_UP") (pin "1") (pinfunction "1_1") (pintype "unspecified"))
      (node (ref "U16") (pin "30") (pinfunction "GPIO19_30") (pintype "bidirectional"))
    )
    (net (code "61") (name "USB2_N") (class "Default")
      (node (ref "FPC4") (pin "5") (pinfunction "5_5") (pintype "input"))
      (node (ref "R48") (pin "2") (pinfunction "2_2") (pintype "input"))
    )
    (net (code "62") (name "USB2_P") (class "Default")
      (node (ref "FPC4") (pin "4") (pinfunction "4_4") (pintype "input"))
      (node (ref "R47") (pin "1") (pinfunction "1_1") (pintype "input"))
    )
    (net (code "63") (name "unconnected-(BACK-Pad1)") (class "Default")
      (node (ref "BACK") (pin "1") (pinfunction "1_1") (pintype "unspecified"))
    )
    (net (code "64") (name "unconnected-(DPAD_DOWN-Pad2)") (class "Default")
      (node (ref "DPAD_DOWN") (pin "2") (pinfunction "2_2") (pintype "unspecified"))
    )
    (net (code "65") (name "unconnected-(DPAD_LEFT-Pad2)") (class "Default")
      (node (ref "DPAD_LEFT") (pin "2") (pinfunction "2_2") (pintype "unspecified"))
    )
    (net (code "66") (name "unconnected-(DPAD_RIGHT-Pad1)") (class "Default")
      (node (ref "DPAD_RIGHT") (pin "1") (pinfunction "1_1") (pintype "unspecified"))
    )
    (net (code "67") (name "unconnected-(DPAD_UP-Pad2)") (class "Default")
      (node (ref "DPAD_UP") (pin "2") (pinfunction "2_2") (pintype "unspecified"))
    )
    (net (code "68") (name "unconnected-(FPC4-Pad23)") (class "Default")
      (node (ref "FPC4") (pin "23") (pinfunction "23_23") (pintype "input"))
    )
    (net (code "69") (name "unconnected-(FPC4-Pad24)") (class "Default")
      (node (ref "FPC4") (pin "24") (pinfunction "24_24") (pintype "input"))
    )
    (net (code "70") (name "unconnected-(FPC5-Pad23)") (class "Default")
      (node (ref "FPC5") (pin "23") (pinfunction "23_23") (pintype "input"))
    )
    (net (code "71") (name "unconnected-(FPC5-Pad24)") (class "Default")
      (node (ref "FPC5") (pin "24") (pinfunction "24_24") (pintype "input"))
    )
    (net (code "72") (name "unconnected-(LB-Pad3)") (class "Default")
      (node (ref "LB") (pin "3") (pinfunction "3_3") (pintype "unspecified"))
    )
    (net (code "73") (name "unconnected-(LB-Pad4)") (class "Default")
      (node (ref "LB") (pin "4") (pinfunction "4_4") (pintype "unspecified"))
    )
    (net (code "74") (name "unconnected-(LT-Pad3)") (class "Default")
      (node (ref "LT") (pin "3") (pinfunction "3_3") (pintype "unspecified"))
    )
    (net (code "75") (name "unconnected-(LT-Pad4)") (class "Default")
      (node (ref "LT") (pin "4") (pinfunction "4_4") (pintype "unspecified"))
    )
    (net (code "76") (name "unconnected-(OPTION1-Pad2)") (class "Default")
      (node (ref "OPTION1") (pin "2") (pinfunction "2_2") (pintype "unspecified"))
    )
    (net (code "77") (name "unconnected-(OPTION1-Pad3)") (class "Default")
      (node (ref "OPTION1") (pin "3") (pinfunction "3_3") (pintype "unspecified"))
    )
    (net (code "78") (name "unconnected-(START-Pad1)") (class "Default")
      (node (ref "START") (pin "1") (pinfunction "1_1") (pintype "unspecified"))
    )
    (net (code "79") (name "unconnected-(STICK-L-Pad5)") (class "Default")
      (node (ref "STICK-L") (pin "5") (pinfunction "5_5") (pintype "unspecified"))
    )
    (net (code "80") (name "unconnected-(STICK-L-Pad6)") (class "Default")
      (node (ref "STICK-L") (pin "6") (pinfunction "6_6") (pintype "unspecified"))
    )
    (net (code "81") (name "unconnected-(U1-FAULT#-Pad4)") (class "Default")
      (node (ref "U1") (pin "4") (pinfunction "FAULT#_4") (pintype "unspecified"))
    )
    (net (code "82") (name "unconnected-(U16-GPIO0-Pad2)") (class "Default")
      (node (ref "U16") (pin "2") (pinfunction "GPIO0_2") (pintype "bidirectional+no_connect"))
    )
    (net (code "83") (name "unconnected-(U16-GPIO1-Pad3)") (class "Default")
      (node (ref "U16") (pin "3") (pinfunction "GPIO1_3") (pintype "bidirectional+no_connect"))
    )
    (net (code "84") (name "unconnected-(U16-GPIO2-Pad4)") (class "Default")
      (node (ref "U16") (pin "4") (pinfunction "GPIO2_4") (pintype "bidirectional+no_connect"))
    )
    (net (code "85") (name "unconnected-(U16-GPIO3-Pad5)") (class "Default")
      (node (ref "U16") (pin "5") (pinfunction "GPIO3_5") (pintype "bidirectional+no_connect"))
    )
    (net (code "86") (name "unconnected-(U16-GPIO4-Pad6)") (class "Default")
      (node (ref "U16") (pin "6") (pinfunction "GPIO4_6") (pintype "bidirectional+no_connect"))
    )
    (net (code "87") (name "unconnected-(U16-SWCLK-Pad24)") (class "Default")
      (node (ref "U16") (pin "24") (pinfunction "SWCLK_24") (pintype "output+no_connect"))
    )
    (net (code "88") (name "unconnected-(U16-SWD-Pad25)") (class "Default")
      (node (ref "U16") (pin "25") (pinfunction "SWD_25") (pintype "bidirectional+no_connect"))
    )
    (net (code "89") (name "unconnected-(U18-NC-Pad4)") (class "Default")
      (node (ref "U18") (pin "4") (pinfunction "NC_4") (pintype "unspecified"))
    )
    (net (code "90") (name "unconnected-(USBC2-SBU1-PadA8)") (class "Default")
      (node (ref "USBC2") (pin "A8") (pinfunction "SBU1_A8") (pintype "unspecified+no_connect"))
    )
    (net (code "91") (name "unconnected-(USBC2-SBU2-PadB8)") (class "Default")
      (node (ref "USBC2") (pin "B8") (pinfunction "SBU2_B8") (pintype "unspecified+no_connect"))
    )
    (net (code "92") (name "unconnected-(X1-GND-Pad2)") (class "Default")
      (node (ref "X1") (pin "2") (pinfunction "GND_2") (pintype "unspecified+no_connect"))
    )
    (net (code "93") (name "unconnected-(X1-GND-Pad4)") (class "Default")
      (node (ref "X1") (pin "4") (pinfunction "GND_4") (pintype "unspecified+no_connect"))
    )
  )
)
